# AnalogConnector.net
KiCad netlist of a schematic drawn in Altium Designer
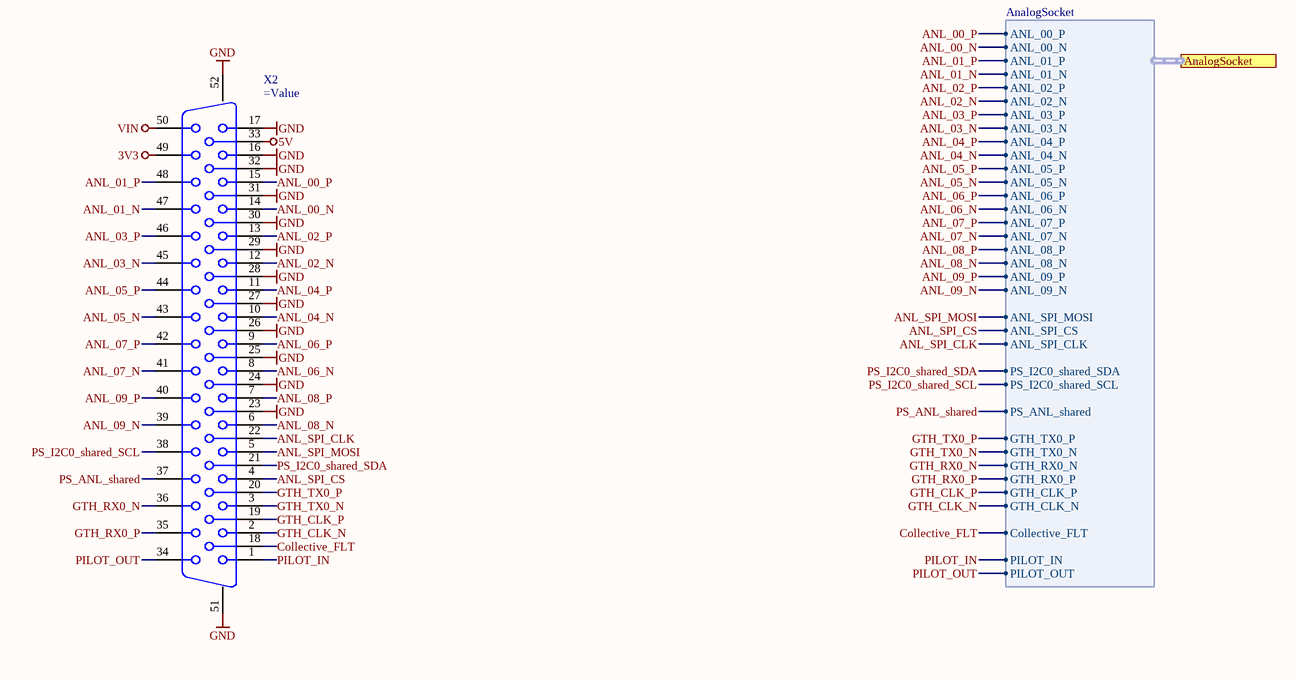
[diagram p0: AnalogConnector.SchDoc]

(export (version "E")
  (design (tool "Eeschema 10.0.6"))
  (components
    (comp (ref "X2")
      (value "~")
      (footprint "dsub50_male_163A18339X")
      (description "D-Sub Standard Connectors DSUB SOLDER PIN ANG 9.4mm")
      (fields
        (field (name "MF") "CONEC")
        (field (name "MPN") "163A18339X")
        (field (name "CREATED") "2021_03_25_AGeiger")
        (field (name "CREATED FROM") "AGeiger")
      )
      (libsource (lib "user") (part "DSUB50_male"))
    )
  )
  (nets
    (net (code "2") (name "/ANL_00_N") (class "Default")
      (node (ref "X2") (pin "14") (pinfunction "14_14") (pintype "passive"))
    )
    (net (code "3") (name "/ANL_00_P") (class "Default")
      (node (ref "X2") (pin "15") (pinfunction "15_15") (pintype "passive"))
    )
    (net (code "4") (name "/ANL_01_N") (class "Default")
      (node (ref "X2") (pin "47") (pinfunction "47_47") (pintype "passive"))
    )
    (net (code "5") (name "/ANL_01_P") (class "Default")
      (node (ref "X2") (pin "48") (pinfunction "48_48") (pintype "passive"))
    )
    (net (code "6") (name "/ANL_02_N") (class "Default")
      (node (ref "X2") (pin "12") (pinfunction "12_12") (pintype "passive"))
    )
    (net (code "7") (name "/ANL_02_P") (class "Default")
      (node (ref "X2") (pin "13") (pinfunction "13_13") (pintype "passive"))
    )
    (net (code "8") (name "/ANL_03_N") (class "Default")
      (node (ref "X2") (pin "45") (pinfunction "45_45") (pintype "passive"))
    )
    (net (code "9") (name "/ANL_03_P") (class "Default")
      (node (ref "X2") (pin "46") (pinfunction "46_46") (pintype "passive"))
    )
    (net (code "10") (name "/ANL_04_N") (class "Default")
      (node (ref "X2") (pin "10") (pinfunction "10_10") (pintype "passive"))
    )
    (net (code "11") (name "/ANL_04_P") (class "Default")
      (node (ref "X2") (pin "11") (pinfunction "11_11") (pintype "passive"))
    )
    (net (code "12") (name "/ANL_05_N") (class "Default")
      (node (ref "X2") (pin "43") (pinfunction "43_43") (pintype "passive"))
    )
    (net (code "13") (name "/ANL_05_P") (class "Default")
      (node (ref "X2") (pin "44") (pinfunction "44_44") (pintype "passive"))
    )
    (net (code "14") (name "/ANL_06_N") (class "Default")
      (node (ref "X2") (pin "8") (pinfunction "8_8") (pintype "passive"))
    )
    (net (code "15") (name "/ANL_06_P") (class "Default")
      (node (ref "X2") (pin "9") (pinfunction "9_9") (pintype "passive"))
    )
    (net (code "16") (name "/ANL_07_N") (class "Default")
      (node (ref "X2") (pin "41") (pinfunction "41_41") (pintype "passive"))
    )
    (net (code "17") (name "/ANL_07_P") (class "Default")
      (node (ref "X2") (pin "42") (pinfunction "42_42") (pintype "passive"))
    )
    (net (code "18") (name "/ANL_08_N") (class "Default")
      (node (ref "X2") (pin "6") (pinfunction "6_6") (pintype "passive"))
    )
    (net (code "19") (name "/ANL_08_P") (class "Default")
      (node (ref "X2") (pin "7") (pinfunction "7_7") (pintype "passive"))
    )
    (net (code "20") (name "/ANL_09_N") (class "Default")
      (node (ref "X2") (pin "39") (pinfunction "39_39") (pintype "passive"))
    )
    (net (code "21") (name "/ANL_09_P") (class "Default")
      (node (ref "X2") (pin "40") (pinfunction "40_40") (pintype "passive"))
    )
    (net (code "22") (name "/ANL_SPI_CLK") (class "Default")
      (node (ref "X2") (pin "22") (pinfunction "22_22") (pintype "passive"))
    )
    (net (code "23") (name "/ANL_SPI_CS") (class "Default")
      (node (ref "X2") (pin "4") (pinfunction "4_4") (pintype "passive"))
    )
    (net (code "24") (name "/ANL_SPI_MOSI") (class "Default")
      (node (ref "X2") (pin "5") (pinfunction "5_5") (pintype "passive"))
    )
    (net (code "25") (name "/Collective_FLT") (class "Default")
      (node (ref "X2") (pin "18") (pinfunction "18_18") (pintype "passive"))
    )
    (net (code "26") (name "/GTH_CLK_N") (class "Default")
      (node (ref "X2") (pin "2") (pinfunction "2_2") (pintype "passive"))
    )
    (net (code "27") (name "/GTH_CLK_P") (class "Default")
      (node (ref "X2") (pin "19") (pinfunction "19_19") (pintype "passive"))
    )
    (net (code "28") (name "/GTH_RX0_N") (class "Default")
      (node (ref "X2") (pin "36") (pinfunction "36_36") (pintype "passive"))
    )
    (net (code "29") (name "/GTH_RX0_P") (class "Default")
      (node (ref "X2") (pin "35") (pinfunction "35_35") (pintype "passive"))
    )
    (net (code "30") (name "/GTH_TX0_N") (class "Default")
      (node (ref "X2") (pin "3") (pinfunction "3_3") (pintype "passive"))
    )
    (net (code "31") (name "/GTH_TX0_P") (class "Default")
      (node (ref "X2") (pin "20") (pinfunction "20_20") (pintype "passive"))
    )
    (net (code "32") (name "/PILOT_IN") (class "Default")
      (node (ref "X2") (pin "1") (pinfunction "1_1") (pintype "passive"))
    )
    (net (code "33") (name "/PILOT_OUT") (class "Default")
      (node (ref "X2") (pin "34") (pinfunction "34_34") (pintype "passive"))
    )
    (net (code "34") (name "/PS_ANL_shared") (class "Default")
      (node (ref "X2") (pin "37") (pinfunction "37_37") (pintype "passive"))
    )
    (net (code "35") (name "/PS_I2C0_shared_SCL") (class "Default")
      (node (ref "X2") (pin "38") (pinfunction "38_38") (pintype "passive"))
    )
    (net (code "36") (name "/PS_I2C0_shared_SDA") (class "Default")
      (node (ref "X2") (pin "21") (pinfunction "21_21") (pintype "passive"))
    )
    (net (code "38") (name "3V3") (class "Default")
      (node (ref "X2") (pin "49") (pinfunction "49_49") (pintype "passive"))
    )
    (net (code "39") (name "5V") (class "Default")
      (node (ref "X2") (pin "33") (pinfunction "33_33") (pintype "passive"))
    )
    (net (code "40") (name "GND") (class "Default")
      (node (ref "X2") (pin "16") (pinfunction "16_16") (pintype "passive"))
      (node (ref "X2") (pin "17") (pinfunction "17_17") (pintype "passive"))
      (node (ref "X2") (pin "23") (pinfunction "23_23") (pintype "passive"))
      (node (ref "X2") (pin "24") (pinfunction "24_24") (pintype "passive"))
      (node (ref "X2") (pin "25") (pinfunction "25_25") (pintype "passive"))
      (node (ref "X2") (pin "26") (pinfunction "26_26") (pintype "passive"))
      (node (ref "X2") (pin "27") (pinfunction "27_27") (pintype "passive"))
      (node (ref "X2") (pin "28") (pinfunction "28_28") (pintype "passive"))
      (node (ref "X2") (pin "29") (pinfunction "29_29") (pintype "passive"))
      (node (ref "X2") (pin "30") (pinfunction "30_30") (pintype "passive"))
      (node (ref "X2") (pin "31") (pinfunction "31_31") (pintype "passive"))
      (node (ref "X2") (pin "32") (pinfunction "32_32") (pintype "passive"))
      (node (ref "X2") (pin "51") (pinfunction "51_51") (pintype "passive"))
      (node (ref "X2") (pin "52") (pinfunction "52_52") (pintype "passive"))
    )
    (net (code "41") (name "VIN") (class "Default")
      (node (ref "X2") (pin "50") (pinfunction "50_50") (pintype "passive"))
    )
  )
)
